# Interfaz_Motor_Maxon.net
KiCad netlist of a schematic drawn in EAGLE
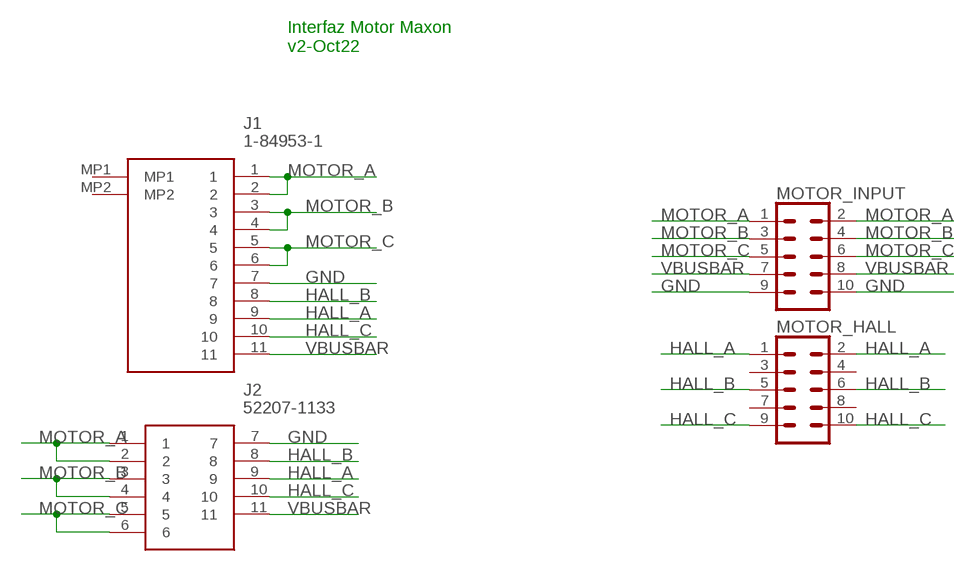
[diagram p0: schematic, sheet 1]

(export (version "E")
  (design (tool "Eeschema 10.0.6"))
  (components
    (comp (ref "J1")
      (value "1-84953-1")
      (footprint "eagle-import:1849531")
      (fields (field (name "MOUSER_PART_NUMBER") "571-1-84953-1"))
      (libsource (lib "eagle-import") (part "1-84953-1"))
    )
    (comp (ref "J2")
      (value "52207-1133")
      (footprint "eagle-import:52207-1133")
      (fields (field (name "MOUSER_PART_NUMBER") "538-52207-1133"))
      (libsource (lib "eagle-import") (part "52207-1133"))
    )
    (comp (ref "MOTOR_HALL")
      (value "CONN_05X2PTH")
      (footprint "eagle-import:2X5")
      (libsource (lib "eagle-import") (part "CONN_05X2PTH"))
    )
    (comp (ref "MOTOR_INPUT")
      (value "CONN_05X2PTH")
      (footprint "eagle-import:2X5")
      (libsource (lib "eagle-import") (part "CONN_05X2PTH"))
    )
  )
  (nets
    (net (code "1") (name "/GND") (class "Default")
      (node (ref "J1") (pin "7") (pinfunction "7_7") (pintype "bidirectional"))
      (node (ref "J2") (pin "7") (pinfunction "7_7") (pintype "bidirectional"))
      (node (ref "MOTOR_INPUT") (pin "10") (pinfunction "10_10") (pintype "passive"))
      (node (ref "MOTOR_INPUT") (pin "9") (pinfunction "9_9") (pintype "passive"))
    )
    (net (code "2") (name "/HALL_A") (class "Default")
      (node (ref "J1") (pin "9") (pinfunction "9_9") (pintype "bidirectional"))
      (node (ref "J2") (pin "9") (pinfunction "9_9") (pintype "bidirectional"))
      (node (ref "MOTOR_HALL") (pin "1") (pinfunction "1_1") (pintype "passive"))
      (node (ref "MOTOR_HALL") (pin "2") (pinfunction "2_2") (pintype "passive"))
    )
    (net (code "3") (name "/HALL_B") (class "Default")
      (node (ref "J1") (pin "8") (pinfunction "8_8") (pintype "bidirectional"))
      (node (ref "J2") (pin "8") (pinfunction "8_8") (pintype "bidirectional"))
      (node (ref "MOTOR_HALL") (pin "5") (pinfunction "5_5") (pintype "passive"))
      (node (ref "MOTOR_HALL") (pin "6") (pinfunction "6_6") (pintype "passive"))
    )
    (net (code "4") (name "/HALL_C") (class "Default")
      (node (ref "J1") (pin "10") (pinfunction "10_10") (pintype "bidirectional"))
      (node (ref "J2") (pin "10") (pinfunction "10_10") (pintype "bidirectional"))
      (node (ref "MOTOR_HALL") (pin "10") (pinfunction "10_10") (pintype "passive"))
      (node (ref "MOTOR_HALL") (pin "9") (pinfunction "9_9") (pintype "passive"))
    )
    (net (code "5") (name "/MOTOR_A") (class "Default")
      (node (ref "J1") (pin "1") (pinfunction "1_1") (pintype "bidirectional"))
      (node (ref "J1") (pin "2") (pinfunction "2_2") (pintype "bidirectional"))
      (node (ref "J2") (pin "1") (pinfunction "1_1") (pintype "bidirectional"))
      (node (ref "J2") (pin "2") (pinfunction "2_2") (pintype "bidirectional"))
      (node (ref "MOTOR_INPUT") (pin "1") (pinfunction "1_1") (pintype "passive"))
      (node (ref "MOTOR_INPUT") (pin "2") (pinfunction "2_2") (pintype "passive"))
    )
    (net (code "6") (name "/MOTOR_B") (class "Default")
      (node (ref "J1") (pin "3") (pinfunction "3_3") (pintype "bidirectional"))
      (node (ref "J1") (pin "4") (pinfunction "4_4") (pintype "bidirectional"))
      (node (ref "J2") (pin "3") (pinfunction "3_3") (pintype "bidirectional"))
      (node (ref "J2") (pin "4") (pinfunction "4_4") (pintype "bidirectional"))
      (node (ref "MOTOR_INPUT") (pin "3") (pinfunction "3_3") (pintype "passive"))
      (node (ref "MOTOR_INPUT") (pin "4") (pinfunction "4_4") (pintype "passive"))
    )
    (net (code "7") (name "/MOTOR_C") (class "Default")
      (node (ref "J1") (pin "5") (pinfunction "5_5") (pintype "bidirectional"))
      (node (ref "J1") (pin "6") (pinfunction "6_6") (pintype "bidirectional"))
      (node (ref "J2") (pin "5") (pinfunction "5_5") (pintype "bidirectional"))
      (node (ref "J2") (pin "6") (pinfunction "6_6") (pintype "bidirectional"))
      (node (ref "MOTOR_INPUT") (pin "5") (pinfunction "5_5") (pintype "passive"))
      (node (ref "MOTOR_INPUT") (pin "6") (pinfunction "6_6") (pintype "passive"))
    )
    (net (code "8") (name "/VBUSBAR") (class "Default")
      (node (ref "J1") (pin "11") (pinfunction "11_11") (pintype "bidirectional"))
      (node (ref "J2") (pin "11") (pinfunction "11_11") (pintype "bidirectional"))
      (node (ref "MOTOR_INPUT") (pin "7") (pinfunction "7_7") (pintype "passive"))
      (node (ref "MOTOR_INPUT") (pin "8") (pinfunction "8_8") (pintype "passive"))
    )
    (net (code "9") (name "unconnected-(J1-PadMP1)") (class "Default")
      (node (ref "J1") (pin "MP1") (pinfunction "MP1_MP1") (pintype "bidirectional"))
    )
    (net (code "10") (name "unconnected-(J1-PadMP2)") (class "Default")
      (node (ref "J1") (pin "MP2") (pinfunction "MP2_MP2") (pintype "bidirectional"))
    )
    (net (code "11") (name "unconnected-(MOTOR_HALL-Pad3)") (class "Default")
      (node (ref "MOTOR_HALL") (pin "3") (pinfunction "3_3") (pintype "passive"))
    )
    (net (code "12") (name "unconnected-(MOTOR_HALL-Pad4)") (class "Default")
      (node (ref "MOTOR_HALL") (pin "4") (pinfunction "4_4") (pintype "passive"))
    )
    (net (code "13") (name "unconnected-(MOTOR_HALL-Pad7)") (class "Default")
      (node (ref "MOTOR_HALL") (pin "7") (pinfunction "7_7") (pintype "passive"))
    )
    (net (code "14") (name "unconnected-(MOTOR_HALL-Pad8)") (class "Default")
      (node (ref "MOTOR_HALL") (pin "8") (pinfunction "8_8") (pintype "passive"))
    )
  )
)
